# SensoCard-Schematic-EasyEDA.net
KiCad netlist of a schematic drawn in EasyEDA
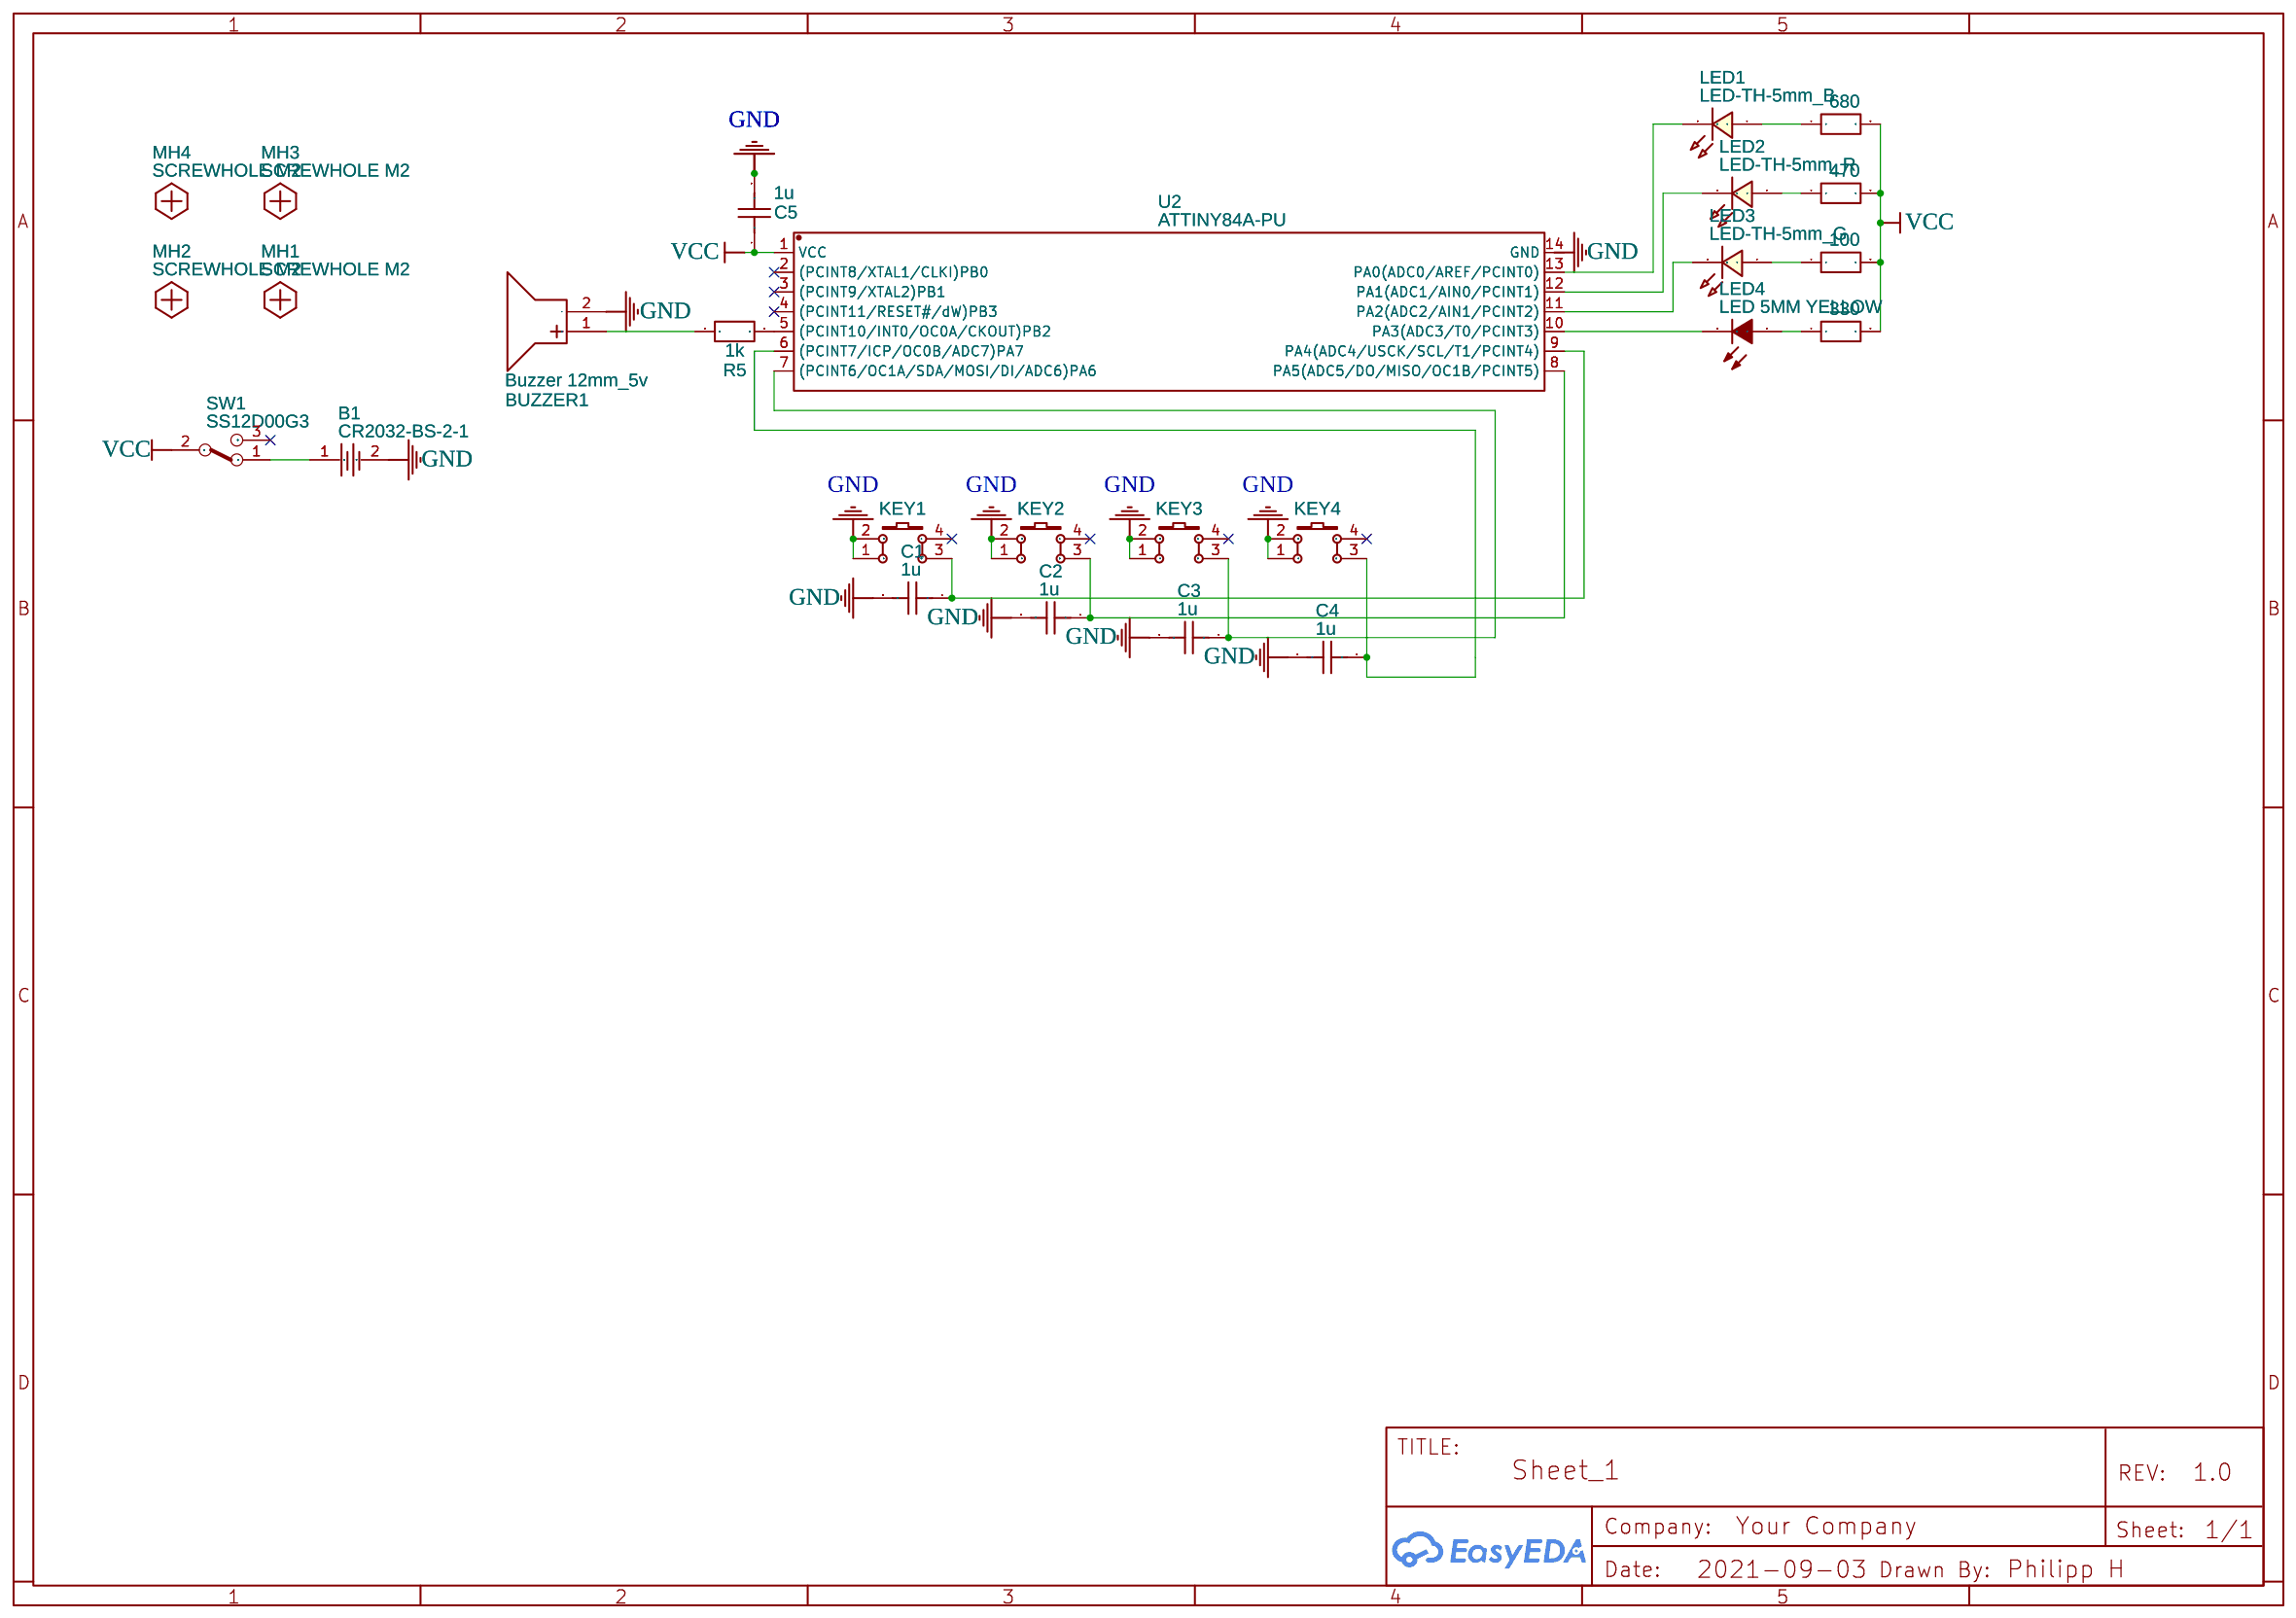
[diagram p0: schematic sheet]

(export (version "E")
  (design (tool "Eeschema 10.0.6"))
  (components
    (comp (ref "B1")
      (value "CR2032-BS-2-1")
      (fields (field (name "BOM_Manufacturer Part") "BS-2-1") (field (name "BOM_Supplier Part") "C70376"))
      (libsource (lib "") (part "CR2032-BS-2-1"))
    )
    (comp (ref "BUZZER1")
      (value "Buzzer 12mm_5v")
      (fields
        (field (name "BOM_Manufacturer Part") "BL-PBZ09042C2703YB")
        (field (name "BOM_Supplier Part") "C187873")
      )
      (libsource (lib "") (part "Buzzer 12mm_5v"))
    )
    (comp (ref "C1") (value "1u") (libsource (lib "") (part "C_RAD-0.1_US")))
    (comp (ref "C2") (value "1u") (libsource (lib "") (part "C_RAD-0.1_US")))
    (comp (ref "C3") (value "1u") (libsource (lib "") (part "C_RAD-0.1_US")))
    (comp (ref "C4") (value "1u") (libsource (lib "") (part "C_RAD-0.1_US")))
    (comp (ref "C5") (value "1u") (libsource (lib "") (part "C_RAD-0.1_US_1")))
    (comp (ref "KEY1")
      (value "K4-12×12_TH")
      (fields
        (field (name "BOM_Manufacturer Part") "K2-1103DP-M4SW-04")
        (field (name "BOM_Supplier Part") "C128053")
      )
      (libsource (lib "") (part "K4-12×12_TH"))
    )
    (comp (ref "KEY2")
      (value "K4-12×12_TH")
      (fields
        (field (name "BOM_Manufacturer Part") "K2-1103DP-M4SW-04")
        (field (name "BOM_Supplier Part") "C128053")
      )
      (libsource (lib "") (part "K4-12×12_TH"))
    )
    (comp (ref "KEY3")
      (value "K4-12×12_TH")
      (fields
        (field (name "BOM_Manufacturer Part") "K2-1103DP-M4SW-04")
        (field (name "BOM_Supplier Part") "C128053")
      )
      (libsource (lib "") (part "K4-12×12_TH"))
    )
    (comp (ref "KEY4")
      (value "K4-12×12_TH")
      (fields
        (field (name "BOM_Manufacturer Part") "K2-1103DP-M4SW-04")
        (field (name "BOM_Supplier Part") "C128053")
      )
      (libsource (lib "") (part "K4-12×12_TH"))
    )
    (comp (ref "LED1") (value "LED-TH-5mm_B") (libsource (lib "") (part "LED-TH-5mm_B")))
    (comp (ref "LED2")
      (value "LED-TH-5mm_R")
      (fields
        (field (name "BOM_Manufacturer Part") "333-2SURD/S530-A3")
        (field (name "BOM_Supplier Part") "C87271")
      )
      (libsource (lib "") (part "LED-TH-5mm_R"))
    )
    (comp (ref "LED3")
      (value "LED-TH-5mm_G")
      (fields
        (field (name "BOM_Manufacturer Part") "333-2SYGD/S530-E2")
        (field (name "BOM_Supplier Part") "C88163")
      )
      (libsource (lib "") (part "LED-TH-5mm_G"))
    )
    (comp (ref "LED4") (value "LED 5MM YELLOW") (libsource (lib "") (part "LED 5MM YELLOW")))
    (comp (ref "MH1") (value "SCREWHOLE M2") (libsource (lib "") (part "SCREWHOLE M2")))
    (comp (ref "MH2") (value "SCREWHOLE M2") (libsource (lib "") (part "SCREWHOLE M2")))
    (comp (ref "MH3") (value "SCREWHOLE M2") (libsource (lib "") (part "SCREWHOLE M2")))
    (comp (ref "MH4") (value "SCREWHOLE M2") (libsource (lib "") (part "SCREWHOLE M2")))
    (comp (ref "R1") (value "680") (libsource (lib "") (part "R_AXIAL-0.3_EU")))
    (comp (ref "R2") (value "470") (libsource (lib "") (part "R_AXIAL-0.3_EU")))
    (comp (ref "R3") (value "100") (libsource (lib "") (part "R_AXIAL-0.3_EU")))
    (comp (ref "R4") (value "330") (libsource (lib "") (part "R_AXIAL-0.3_EU")))
    (comp (ref "R5") (value "1k") (libsource (lib "") (part "R_AXIAL-0.3_EU")))
    (comp (ref "SW1")
      (value "SS12D00G3")
      (fields (field (name "BOM_Manufacturer Part") "Switch SPDT"))
      (libsource (lib "") (part "SS12D00G3"))
    )
    (comp (ref "U2")
      (value "ATTINY84A-PU")
      (fields (field (name "BOM_Supplier Part") "C145560"))
      (libsource (lib "") (part "ATTINY84A-PU"))
    )
  )
  (nets
    (net (code "1") (name "GND") (class "Default")
      (node (ref "B1") (pin "2") (pinfunction "2_2") (pintype "input"))
      (node (ref "BUZZER1") (pin "2") (pinfunction "-_2") (pintype "unspecified"))
      (node (ref "C1") (pin "2") (pinfunction "2_2") (pintype "unspecified"))
      (node (ref "C2") (pin "2") (pinfunction "2_2") (pintype "unspecified"))
      (node (ref "C3") (pin "2") (pinfunction "2_2") (pintype "unspecified"))
      (node (ref "C4") (pin "2") (pinfunction "2_2") (pintype "unspecified"))
      (node (ref "C5") (pin "2") (pinfunction "2_2") (pintype "unspecified"))
      (node (ref "KEY1") (pin "1") (pinfunction "1_1") (pintype "unspecified"))
      (node (ref "KEY1") (pin "2") (pinfunction "2_2") (pintype "unspecified"))
      (node (ref "KEY2") (pin "1") (pinfunction "1_1") (pintype "unspecified"))
      (node (ref "KEY2") (pin "2") (pinfunction "2_2") (pintype "unspecified"))
      (node (ref "KEY3") (pin "1") (pinfunction "1_1") (pintype "unspecified"))
      (node (ref "KEY3") (pin "2") (pinfunction "2_2") (pintype "unspecified"))
      (node (ref "KEY4") (pin "1") (pinfunction "1_1") (pintype "unspecified"))
      (node (ref "KEY4") (pin "2") (pinfunction "2_2") (pintype "unspecified"))
      (node (ref "U2") (pin "14") (pinfunction "GND_14") (pintype "unspecified"))
    )
    (net (code "2") (name "Net-(BUZZER1-+)") (class "Default")
      (node (ref "BUZZER1") (pin "1") (pinfunction "+_1") (pintype "unspecified"))
      (node (ref "R5") (pin "1") (pinfunction "1_1") (pintype "unspecified"))
    )
    (net (code "3") (name "Net-(LED1-Pad1)") (class "Default")
      (node (ref "LED1") (pin "1") (pinfunction "1_1") (pintype "unspecified"))
      (node (ref "R1") (pin "1") (pinfunction "1_1") (pintype "unspecified"))
    )
    (net (code "4") (name "Net-(LED2-Pad1)") (class "Default")
      (node (ref "LED2") (pin "1") (pinfunction "1_1") (pintype "unspecified"))
      (node (ref "R2") (pin "1") (pinfunction "1_1") (pintype "unspecified"))
    )
    (net (code "5") (name "Net-(LED3-Pad1)") (class "Default")
      (node (ref "LED3") (pin "1") (pinfunction "1_1") (pintype "unspecified"))
      (node (ref "R3") (pin "1") (pinfunction "1_1") (pintype "unspecified"))
    )
    (net (code "6") (name "Net-(LED4-A)") (class "Default")
      (node (ref "LED4") (pin "1") (pinfunction "A_1") (pintype "input"))
      (node (ref "R4") (pin "1") (pinfunction "1_1") (pintype "unspecified"))
    )
    (net (code "7") (name "Net-(LED4-K)") (class "Default")
      (node (ref "LED4") (pin "2") (pinfunction "K_2") (pintype "input"))
      (node (ref "U2") (pin "10") (pinfunction "PA3(ADC3/T0/PCINT3)_10") (pintype "unspecified"))
    )
    (net (code "8") (name "Net-(SW1-C)") (class "Default")
      (node (ref "B1") (pin "1") (pinfunction "1_1") (pintype "input"))
      (node (ref "SW1") (pin "1") (pinfunction "C_1") (pintype "unspecified"))
    )
    (net (code "9") (name "Net-(U2-(PCINT6{slash}OC1A{slash}SDA{slash}MOSI{slash}DI{slash}ADC6)PA6)") (class "Default")
      (node (ref "C3") (pin "1") (pinfunction "1_1") (pintype "unspecified"))
      (node (ref "KEY3") (pin "3") (pinfunction "3_3") (pintype "unspecified"))
      (node (ref "U2") (pin "7") (pinfunction "(PCINT6/OC1A/SDA/MOSI/DI/ADC6)PA6_7") (pintype "unspecified"))
    )
    (net (code "10") (name "Net-(U2-(PCINT7{slash}ICP{slash}OC0B{slash}ADC7)PA7)") (class "Default")
      (node (ref "C4") (pin "1") (pinfunction "1_1") (pintype "unspecified"))
      (node (ref "KEY4") (pin "3") (pinfunction "3_3") (pintype "unspecified"))
      (node (ref "U2") (pin "6") (pinfunction "(PCINT7/ICP/OC0B/ADC7)PA7_6") (pintype "unspecified"))
    )
    (net (code "11") (name "Net-(U2-(PCINT10{slash}INT0{slash}OC0A{slash}CKOUT)PB2)") (class "Default")
      (node (ref "R5") (pin "2") (pinfunction "2_2") (pintype "unspecified"))
      (node (ref "U2") (pin "5") (pinfunction "(PCINT10/INT0/OC0A/CKOUT)PB2_5") (pintype "unspecified"))
    )
    (net (code "12") (name "Net-(U2-PA0(ADC0{slash}AREF{slash}PCINT0))") (class "Default")
      (node (ref "LED1") (pin "2") (pinfunction "2_2") (pintype "unspecified"))
      (node (ref "U2") (pin "13") (pinfunction "PA0(ADC0/AREF/PCINT0)_13") (pintype "unspecified"))
    )
    (net (code "13") (name "Net-(U2-PA1(ADC1{slash}AIN0{slash}PCINT1))") (class "Default")
      (node (ref "LED2") (pin "2") (pinfunction "2_2") (pintype "unspecified"))
      (node (ref "U2") (pin "12") (pinfunction "PA1(ADC1/AIN0/PCINT1)_12") (pintype "unspecified"))
    )
    (net (code "14") (name "Net-(U2-PA2(ADC2{slash}AIN1{slash}PCINT2))") (class "Default")
      (node (ref "LED3") (pin "2") (pinfunction "2_2") (pintype "unspecified"))
      (node (ref "U2") (pin "11") (pinfunction "PA2(ADC2/AIN1/PCINT2)_11") (pintype "unspecified"))
    )
    (net (code "15") (name "Net-(U2-PA4(ADC4{slash}USCK{slash}SCL{slash}T1{slash}PCINT4))") (class "Default")
      (node (ref "C1") (pin "1") (pinfunction "1_1") (pintype "unspecified"))
      (node (ref "KEY1") (pin "3") (pinfunction "3_3") (pintype "unspecified"))
      (node (ref "U2") (pin "9") (pinfunction "PA4(ADC4/USCK/SCL/T1/PCINT4)_9") (pintype "unspecified"))
    )
    (net (code "16") (name "Net-(U2-PA5(ADC5{slash}DO{slash}MISO{slash}OC1B{slash}PCINT5))") (class "Default")
      (node (ref "C2") (pin "1") (pinfunction "1_1") (pintype "unspecified"))
      (node (ref "KEY2") (pin "3") (pinfunction "3_3") (pintype "unspecified"))
      (node (ref "U2") (pin "8") (pinfunction "PA5(ADC5/DO/MISO/OC1B/PCINT5)_8") (pintype "unspecified"))
    )
    (net (code "17") (name "VCC") (class "Default")
      (node (ref "C5") (pin "1") (pinfunction "1_1") (pintype "unspecified"))
      (node (ref "R1") (pin "2") (pinfunction "2_2") (pintype "unspecified"))
      (node (ref "R2") (pin "2") (pinfunction "2_2") (pintype "unspecified"))
      (node (ref "R3") (pin "2") (pinfunction "2_2") (pintype "unspecified"))
      (node (ref "R4") (pin "2") (pinfunction "2_2") (pintype "unspecified"))
      (node (ref "SW1") (pin "2") (pinfunction "NC_2") (pintype "unspecified"))
      (node (ref "U2") (pin "1") (pinfunction "VCC_1") (pintype "unspecified"))
    )
    (net (code "18") (name "unconnected-(KEY1-Pad4)") (class "Default")
      (node (ref "KEY1") (pin "4") (pinfunction "4_4") (pintype "unspecified+no_connect"))
    )
    (net (code "19") (name "unconnected-(KEY2-Pad4)") (class "Default")
      (node (ref "KEY2") (pin "4") (pinfunction "4_4") (pintype "unspecified+no_connect"))
    )
    (net (code "20") (name "unconnected-(KEY3-Pad4)") (class "Default")
      (node (ref "KEY3") (pin "4") (pinfunction "4_4") (pintype "unspecified+no_connect"))
    )
    (net (code "21") (name "unconnected-(KEY4-Pad4)") (class "Default")
      (node (ref "KEY4") (pin "4") (pinfunction "4_4") (pintype "unspecified+no_connect"))
    )
    (net (code "22") (name "unconnected-(SW1-NO-Pad3)") (class "Default")
      (node (ref "SW1") (pin "3") (pinfunction "NO_3") (pintype "unspecified+no_connect"))
    )
    (net (code "23") (name "unconnected-(U2-(PCINT8{slash}XTAL1{slash}CLKI)PB0-Pad2)") (class "Default")
      (node (ref "U2") (pin "2") (pinfunction "(PCINT8/XTAL1/CLKI)PB0_2") (pintype "unspecified+no_connect"))
    )
    (net (code "24") (name "unconnected-(U2-(PCINT9{slash}XTAL2)PB1-Pad3)") (class "Default")
      (node (ref "U2") (pin "3") (pinfunction "(PCINT9/XTAL2)PB1_3") (pintype "unspecified+no_connect"))
    )
    (net (code "25") (name "unconnected-(U2-(PCINT11{slash}RESET#{slash}dW)PB3-Pad4)") (class "Default")
      (node (ref "U2") (pin "4") (pinfunction "(PCINT11/RESET#/dW)PB3_4") (pintype "unspecified+no_connect"))
    )
  )
)
